# ET-DAC.net
KiCad netlist of a schematic drawn in Altium Designer
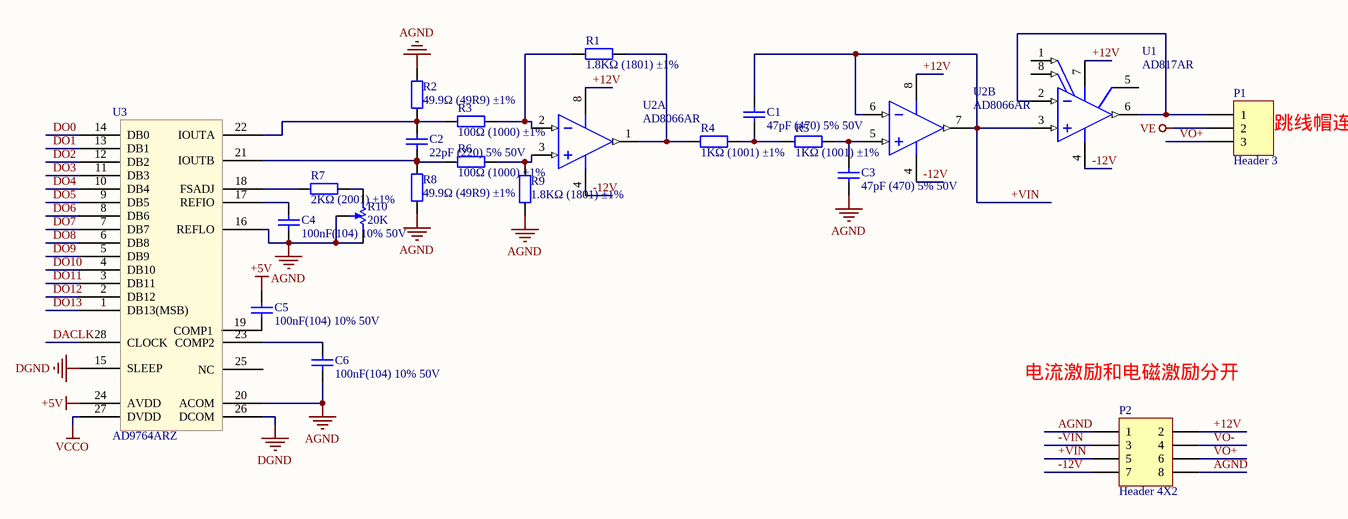
[diagram p0: ET-DAC.SchDoc]

(export (version "E")
  (design (tool "Eeschema 10.0.6"))
  (components
    (comp (ref "C1")
      (value "47pF (470) 5% 50V")
      (footprint "LC-0805_C")
      (description "贴片电容")
      (libsource (lib "Miscellaneous Devices LC") (part "0805 47pF (470) 5% 50V"))
    )
    (comp (ref "C2")
      (value "22pF (220) 5% 50V")
      (footprint "LC-0805_C")
      (description "贴片电容")
      (libsource (lib "Miscellaneous Devices LC") (part "0805 22pF (220) 5% 50V"))
    )
    (comp (ref "C3")
      (value "47pF (470) 5% 50V")
      (footprint "LC-0805_C")
      (description "贴片电容")
      (libsource (lib "Miscellaneous Devices LC") (part "0805 47pF (470) 5% 50V"))
    )
    (comp (ref "C4")
      (value "100nF(104) 10% 50V")
      (footprint "LC-0805_C")
      (description "贴片电容")
      (libsource (lib "Miscellaneous Devices LC") (part "0805 100nF(104) 10% 50V"))
    )
    (comp (ref "C5")
      (value "100nF(104) 10% 50V")
      (footprint "LC-0805_C")
      (description "贴片电容")
      (libsource (lib "Miscellaneous Devices LC") (part "0805 100nF(104) 10% 50V"))
    )
    (comp (ref "C6")
      (value "100nF(104) 10% 50V")
      (footprint "LC-0805_C")
      (description "贴片电容")
      (libsource (lib "Miscellaneous Devices LC") (part "0805 100nF(104) 10% 50V"))
    )
    (comp (ref "P1")
      (value "Header 3")
      (footprint "HDR1X3")
      (description "Header, 3-Pin")
      (fields (field (name "PUBLISHER") "Altium Limited"))
      (libsource (lib "Miscellaneous Connectors") (part "Header 3"))
    )
    (comp (ref "P2")
      (value "Header 4X2")
      (footprint "HDR2X4")
      (description "Header, 4-Pin, Dual row")
      (fields (field (name "PUBLISHER") "Altium Limited"))
      (libsource (lib "Miscellaneous Connectors") (part "Header 4X2"))
    )
    (comp (ref "R1")
      (value "1.8KΩ (1801) ±1%")
      (footprint "LC-0805_R")
      (description "贴片电阻")
      (libsource (lib "") (part "0805 1.8KΩ (1801) 1%_1"))
    )
    (comp (ref "R2")
      (value "49.9Ω (49R9) ±1%")
      (footprint "LC-0805_R")
      (description "贴片电阻")
      (libsource (lib "Miscellaneous Devices LC") (part "0805 49.9Ω (49R9) 1%"))
    )
    (comp (ref "R3")
      (value "100Ω (1000) ±1%")
      (footprint "LC-0805_R")
      (description "贴片电阻")
      (libsource (lib "Miscellaneous Devices LC") (part "0805 100Ω (1000) 1%"))
    )
    (comp (ref "R4")
      (value "1KΩ (1001) ±1%")
      (footprint "LC-0805_R")
      (description "贴片电阻")
      (libsource (lib "") (part "0805 1KΩ (1001) 1%_1"))
    )
    (comp (ref "R5")
      (value "1KΩ (1001) ±1%")
      (footprint "LC-0805_R")
      (description "贴片电阻")
      (libsource (lib "Miscellaneous Devices LC") (part "0805 1KΩ (1001) 1%"))
    )
    (comp (ref "R6")
      (value "100Ω (1000) ±1%")
      (footprint "LC-0805_R")
      (description "贴片电阻")
      (libsource (lib "Miscellaneous Devices LC") (part "0805 100Ω (1000) 1%"))
    )
    (comp (ref "R7")
      (value "2KΩ (2001) ±1%")
      (footprint "LC-0805_R")
      (description "贴片电阻")
      (libsource (lib "Miscellaneous Devices LC") (part "0805 2KΩ (2001) 1%"))
    )
    (comp (ref "R8")
      (value "49.9Ω (49R9) ±1%")
      (footprint "LC-0805_R")
      (description "贴片电阻")
      (libsource (lib "Miscellaneous Devices LC") (part "0805 49.9Ω (49R9) 1%"))
    )
    (comp (ref "R9")
      (value "1.8KΩ (1801) ±1%")
      (footprint "LC-0805_R")
      (description "贴片电阻")
      (libsource (lib "Miscellaneous Devices LC") (part "0805 1.8KΩ (1801) 1%"))
    )
    (comp (ref "R10")
      (value "20K")
      (footprint "POT4MM-2")
      (description "Square Trimming Potentiometer")
      (fields (field (name "PUBLISHER") "Altium Limited"))
      (libsource (lib "Miscellaneous Devices") (part "RPot SM"))
    )
    (comp (ref "U1")
      (value "AD817AR")
      (footprint "ADI-R-8_N")
      (fields (field (name "GENERIC PART NUMBER") "AD817") (field (name "MANUFACTURER") "Analog Devices"))
      (libsource (lib "Analog Devices Operational Amplifiers") (part "AD817AR"))
    )
    (comp (ref "U2")
      (value "AD8066AR")
      (footprint "ADI-R-8_N")
      (fields (field (name "GENERIC PART NUMBER") "AD8066") (field (name "MANUFACTURER") "Analog Devices"))
      (libsource (lib "Analog Devices Operational Amplifiers") (part "AD8066AR"))
    )
    (comp (ref "U3")
      (value "AD9764ARZ")
      (footprint "RU-28_N")
      (description "Imported")
      (libsource (lib "AD9764ARZ") (part "AD9764ARZ"))
    )
  )
  (nets
    (net (code "1") (name "+5V") (class "Default")
      (node (ref "C5") (pin "2") (pinfunction "2_2") (pintype "passive"))
      (node (ref "U3") (pin "24") (pinfunction "AVDD_24") (pintype "power_in"))
    )
    (net (code "2") (name "/+12V") (class "Default")
      (node (ref "P2") (pin "2") (pinfunction "2_2") (pintype "passive"))
      (node (ref "U1") (pin "7") (pinfunction "+VS_7") (pintype "power_in"))
      (node (ref "U2") (pin "8") (pinfunction "+VS_8") (pintype "power_in"))
    )
    (net (code "3") (name "/+VIN") (class "Default")
      (node (ref "C1") (pin "2") (pinfunction "2_2") (pintype "passive"))
      (node (ref "P2") (pin "5") (pinfunction "5_5") (pintype "passive"))
      (node (ref "U1") (pin "3") (pinfunction "+IN_3") (pintype "input"))
      (node (ref "U2") (pin "6") (pinfunction "-IN_2_6") (pintype "input"))
      (node (ref "U2") (pin "7") (pinfunction "VOUT_2_7") (pintype "output"))
    )
    (net (code "4") (name "/-12V") (class "Default")
      (node (ref "P2") (pin "7") (pinfunction "7_7") (pintype "passive"))
      (node (ref "U1") (pin "4") (pinfunction "-VS_4") (pintype "power_in"))
      (node (ref "U2") (pin "4") (pinfunction "-VS_4") (pintype "power_in"))
    )
    (net (code "5") (name "/-VIN") (class "Default")
      (node (ref "P2") (pin "3") (pinfunction "3_3") (pintype "passive"))
    )
    (net (code "6") (name "/DACLK") (class "Default")
      (node (ref "U3") (pin "28") (pinfunction "CLOCK_28") (pintype "passive"))
    )
    (net (code "7") (name "/DO0") (class "Default")
      (node (ref "U3") (pin "14") (pinfunction "DB0_14") (pintype "passive"))
    )
    (net (code "8") (name "/DO1") (class "Default")
      (node (ref "U3") (pin "13") (pinfunction "DB1_13") (pintype "passive"))
    )
    (net (code "9") (name "/DO2") (class "Default")
      (node (ref "U3") (pin "12") (pinfunction "DB2_12") (pintype "passive"))
    )
    (net (code "10") (name "/DO3") (class "Default")
      (node (ref "U3") (pin "11") (pinfunction "DB3_11") (pintype "passive"))
    )
    (net (code "11") (name "/DO4") (class "Default")
      (node (ref "U3") (pin "10") (pinfunction "DB4_10") (pintype "passive"))
    )
    (net (code "12") (name "/DO5") (class "Default")
      (node (ref "U3") (pin "9") (pinfunction "DB5_9") (pintype "passive"))
    )
    (net (code "13") (name "/DO6") (class "Default")
      (node (ref "U3") (pin "8") (pinfunction "DB6_8") (pintype "passive"))
    )
    (net (code "14") (name "/DO7") (class "Default")
      (node (ref "U3") (pin "7") (pinfunction "DB7_7") (pintype "passive"))
    )
    (net (code "15") (name "/DO8") (class "Default")
      (node (ref "U3") (pin "6") (pinfunction "DB8_6") (pintype "passive"))
    )
    (net (code "16") (name "/DO9") (class "Default")
      (node (ref "U3") (pin "5") (pinfunction "DB9_5") (pintype "passive"))
    )
    (net (code "17") (name "/DO10") (class "Default")
      (node (ref "U3") (pin "4") (pinfunction "DB10_4") (pintype "passive"))
    )
    (net (code "18") (name "/DO11") (class "Default")
      (node (ref "U3") (pin "3") (pinfunction "DB11_3") (pintype "passive"))
    )
    (net (code "19") (name "/DO12") (class "Default")
      (node (ref "U3") (pin "2") (pinfunction "DB12_2") (pintype "passive"))
    )
    (net (code "20") (name "/DO13") (class "Default")
      (node (ref "U3") (pin "1") (pinfunction "DB13(MSB)_1") (pintype "passive"))
    )
    (net (code "21") (name "/VO+") (class "Default")
      (node (ref "P1") (pin "3") (pinfunction "3_3") (pintype "passive"))
      (node (ref "P2") (pin "6") (pinfunction "6_6") (pintype "passive"))
    )
    (net (code "22") (name "/VO-") (class "Default")
      (node (ref "P2") (pin "4") (pinfunction "4_4") (pintype "passive"))
    )
    (net (code "23") (name "AGND") (class "Default")
      (node (ref "C3") (pin "2") (pinfunction "2_2") (pintype "passive"))
      (node (ref "C4") (pin "1") (pinfunction "1_1") (pintype "passive"))
      (node (ref "C6") (pin "1") (pinfunction "1_1") (pintype "passive"))
      (node (ref "P2") (pin "1") (pinfunction "1_1") (pintype "passive"))
      (node (ref "P2") (pin "8") (pinfunction "8_8") (pintype "passive"))
      (node (ref "R10") (pin "CW") (pinfunction "+_CW") (pintype "passive"))
      (node (ref "R10") (pin "W") (pinfunction "W_W") (pintype "passive"))
      (node (ref "R2") (pin "2") (pinfunction "2_2") (pintype "passive"))
      (node (ref "R8") (pin "1") (pinfunction "1_1") (pintype "passive"))
      (node (ref "R9") (pin "1") (pinfunction "1_1") (pintype "passive"))
      (node (ref "U3") (pin "16") (pinfunction "REFLO_16") (pintype "passive"))
      (node (ref "U3") (pin "20") (pinfunction "ACOM_20") (pintype "passive"))
    )
    (net (code "24") (name "DGND") (class "Default")
      (node (ref "U3") (pin "15") (pinfunction "SLEEP_15") (pintype "passive"))
      (node (ref "U3") (pin "26") (pinfunction "DCOM_26") (pintype "passive"))
    )
    (net (code "25") (name "Net-(C1-Pad1)") (class "Default")
      (node (ref "C1") (pin "1") (pinfunction "1_1") (pintype "passive"))
      (node (ref "R4") (pin "2") (pinfunction "2_2") (pintype "passive"))
      (node (ref "R5") (pin "2") (pinfunction "2_2") (pintype "passive"))
    )
    (net (code "26") (name "Net-(R10--)") (class "Default")
      (node (ref "R10") (pin "CCW") (pinfunction "-_CCW") (pintype "passive"))
      (node (ref "R7") (pin "2") (pinfunction "2_2") (pintype "passive"))
    )
    (net (code "27") (name "Net-(U1--IN)") (class "Default")
      (node (ref "P1") (pin "1") (pinfunction "1_1") (pintype "passive"))
      (node (ref "U1") (pin "2") (pinfunction "-IN_2") (pintype "input"))
      (node (ref "U1") (pin "6") (pinfunction "OUT_6") (pintype "output"))
    )
    (net (code "28") (name "Net-(U2A-+IN_1)") (class "Default")
      (node (ref "R6") (pin "2") (pinfunction "2_2") (pintype "passive"))
      (node (ref "R9") (pin "2") (pinfunction "2_2") (pintype "passive"))
      (node (ref "U2") (pin "3") (pinfunction "+IN_1_3") (pintype "input"))
    )
    (net (code "29") (name "Net-(U2A--IN_1)") (class "Default")
      (node (ref "R1") (pin "1") (pinfunction "1_1") (pintype "passive"))
      (node (ref "R3") (pin "2") (pinfunction "2_2") (pintype "passive"))
      (node (ref "U2") (pin "2") (pinfunction "-IN_1_2") (pintype "input"))
    )
    (net (code "30") (name "Net-(U2A-VOUT_1)") (class "Default")
      (node (ref "R1") (pin "2") (pinfunction "2_2") (pintype "passive"))
      (node (ref "R4") (pin "1") (pinfunction "1_1") (pintype "passive"))
      (node (ref "U2") (pin "1") (pinfunction "VOUT_1_1") (pintype "output"))
    )
    (net (code "31") (name "Net-(U2B-+IN_2)") (class "Default")
      (node (ref "C3") (pin "1") (pinfunction "1_1") (pintype "passive"))
      (node (ref "R5") (pin "1") (pinfunction "1_1") (pintype "passive"))
      (node (ref "U2") (pin "5") (pinfunction "+IN_2_5") (pintype "input"))
    )
    (net (code "32") (name "Net-(U3-COMP1)") (class "Default")
      (node (ref "C5") (pin "1") (pinfunction "1_1") (pintype "passive"))
      (node (ref "U3") (pin "19") (pinfunction "COMP1_19") (pintype "passive"))
    )
    (net (code "33") (name "Net-(U3-COMP2)") (class "Default")
      (node (ref "C6") (pin "2") (pinfunction "2_2") (pintype "passive"))
      (node (ref "U3") (pin "23") (pinfunction "COMP2_23") (pintype "passive"))
    )
    (net (code "34") (name "Net-(U3-FSADJ)") (class "Default")
      (node (ref "R7") (pin "1") (pinfunction "1_1") (pintype "passive"))
      (node (ref "U3") (pin "18") (pinfunction "FSADJ_18") (pintype "passive"))
    )
    (net (code "35") (name "Net-(U3-IOUTA)") (class "Default")
      (node (ref "C2") (pin "2") (pinfunction "2_2") (pintype "passive"))
      (node (ref "R2") (pin "1") (pinfunction "1_1") (pintype "passive"))
      (node (ref "R3") (pin "1") (pinfunction "1_1") (pintype "passive"))
      (node (ref "U3") (pin "22") (pinfunction "IOUTA_22") (pintype "passive"))
    )
    (net (code "36") (name "Net-(U3-IOUTB)") (class "Default")
      (node (ref "C2") (pin "1") (pinfunction "1_1") (pintype "passive"))
      (node (ref "R6") (pin "1") (pinfunction "1_1") (pintype "passive"))
      (node (ref "R8") (pin "2") (pinfunction "2_2") (pintype "passive"))
      (node (ref "U3") (pin "21") (pinfunction "IOUTB_21") (pintype "passive"))
    )
    (net (code "37") (name "Net-(U3-REFIO)") (class "Default")
      (node (ref "C4") (pin "2") (pinfunction "2_2") (pintype "passive"))
      (node (ref "U3") (pin "17") (pinfunction "REFIO_17") (pintype "passive"))
    )
    (net (code "38") (name "VCCO") (class "Default")
      (node (ref "U3") (pin "27") (pinfunction "DVDD_27") (pintype "power_in"))
    )
    (net (code "39") (name "VE") (class "Default")
      (node (ref "P1") (pin "2") (pinfunction "2_2") (pintype "passive"))
    )
    (net (code "40") (name "unconnected-(U1-NC-Pad5)") (class "Default")
      (node (ref "U1") (pin "5") (pinfunction "NC_5") (pintype "passive"))
    )
    (net (code "41") (name "unconnected-(U1-NULL-Pad1)") (class "Default")
      (node (ref "U1") (pin "1") (pinfunction "NULL_1") (pintype "input"))
    )
    (net (code "42") (name "unconnected-(U1-NULL-Pad8)") (class "Default")
      (node (ref "U1") (pin "8") (pinfunction "NULL_8") (pintype "input"))
    )
    (net (code "43") (name "unconnected-(U3-NC-Pad25)") (class "Default")
      (node (ref "U3") (pin "25") (pinfunction "NC_25") (pintype "passive"))
    )
  )
)
